# mt2.net
KiCad netlist of a schematic drawn in EAGLE
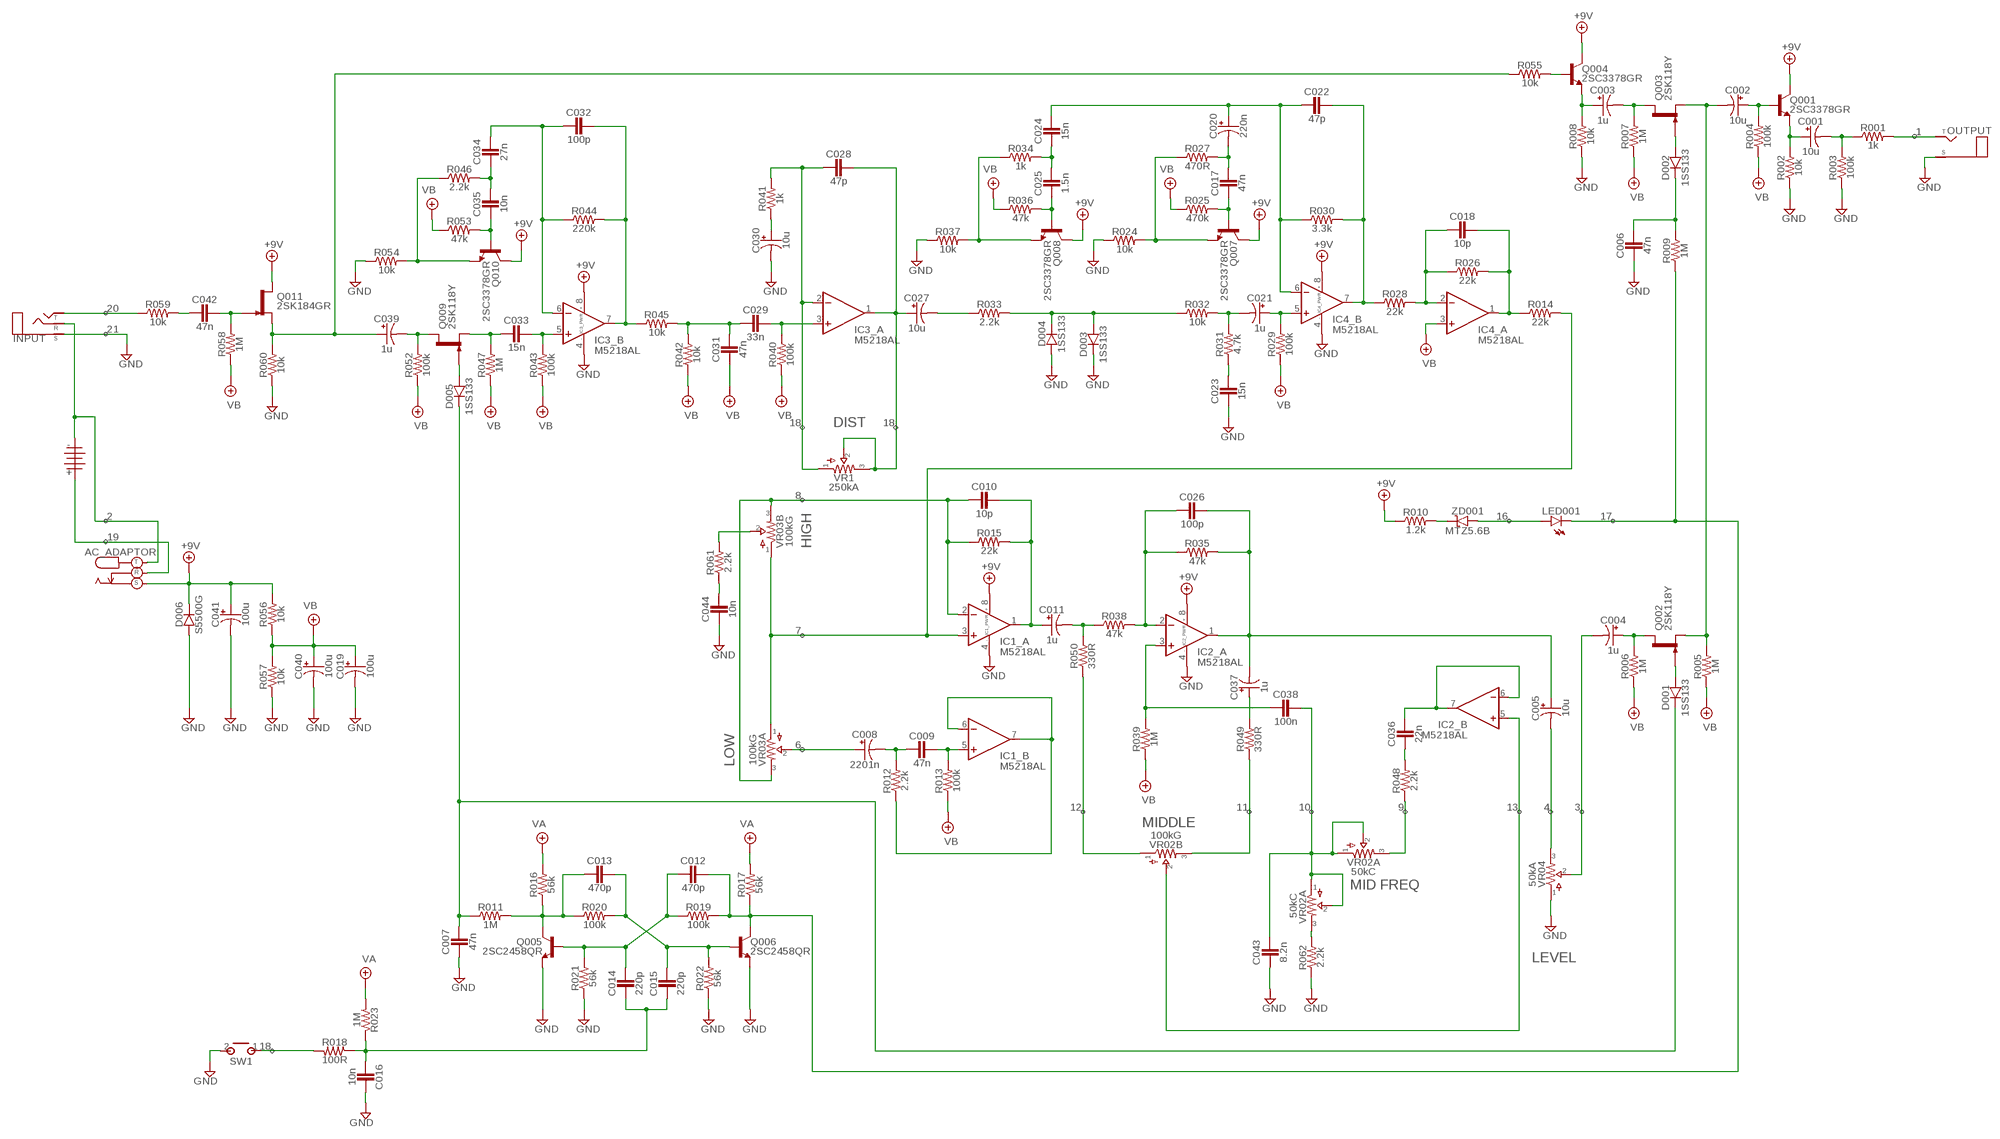
[diagram p0: schematic, sheet 1]

(export (version "E")
  (design (tool "Eeschema 10.0.6"))
  (components
    (comp (ref "1101")
      (value "BATTERY")
      (footprint "eagle-import:TWO_PADS")
      (libsource (lib "eagle-import") (part "BATTERY"))
    )
    (comp (ref "AC_ADAPTOR")
      (value "DC_KOBICONN")
      (footprint "eagle-import:DC_KOBICONN")
      (libsource (lib "eagle-import") (part "DC_KOBICONN"))
    )
    (comp (ref "C001")
      (value "10u")
      (footprint "eagle-import:050_020")
      (libsource (lib "eagle-import") (part "0500"))
    )
    (comp (ref "C002")
      (value "10u")
      (footprint "eagle-import:050_020")
      (libsource (lib "eagle-import") (part "0500"))
    )
    (comp (ref "C003")
      (value "1u")
      (footprint "eagle-import:050_020")
      (libsource (lib "eagle-import") (part "0500"))
    )
    (comp (ref "C004")
      (value "1u")
      (footprint "eagle-import:050_020")
      (libsource (lib "eagle-import") (part "0500"))
    )
    (comp (ref "C005")
      (value "10u")
      (footprint "eagle-import:050_020")
      (libsource (lib "eagle-import") (part "0500"))
    )
    (comp (ref "C006")
      (value "47n")
      (footprint "eagle-import:BOX_SMALL")
      (libsource (lib "eagle-import") (part "CER/FILMBOX.1"))
    )
    (comp (ref "C007")
      (value "47n")
      (footprint "eagle-import:BOX_SMALL")
      (libsource (lib "eagle-import") (part "CER/FILMBOX.1"))
    )
    (comp (ref "C008")
      (value "2201n")
      (footprint "eagle-import:050_020")
      (libsource (lib "eagle-import") (part "0500"))
    )
    (comp (ref "C009")
      (value "47n")
      (footprint "eagle-import:BOX_SMALL")
      (libsource (lib "eagle-import") (part "CER/FILMBOX.1"))
    )
    (comp (ref "C010")
      (value "10p")
      (footprint "eagle-import:BOX_SMALL")
      (libsource (lib "eagle-import") (part "CER/FILMBOX.1"))
    )
    (comp (ref "C011")
      (value "1u")
      (footprint "eagle-import:050_020")
      (libsource (lib "eagle-import") (part "0500"))
    )
    (comp (ref "C012")
      (value "470p")
      (footprint "eagle-import:BOX_SMALL")
      (libsource (lib "eagle-import") (part "CER/FILMBOX.1"))
    )
    (comp (ref "C013")
      (value "470p")
      (footprint "eagle-import:BOX_SMALL")
      (libsource (lib "eagle-import") (part "CER/FILMBOX.1"))
    )
    (comp (ref "C014")
      (value "220p")
      (footprint "eagle-import:BOX_SMALL")
      (libsource (lib "eagle-import") (part "CER/FILMBOX.1"))
    )
    (comp (ref "C015")
      (value "220p")
      (footprint "eagle-import:BOX_SMALL")
      (libsource (lib "eagle-import") (part "CER/FILMBOX.1"))
    )
    (comp (ref "C016")
      (value "10n")
      (footprint "eagle-import:BOX_SMALL")
      (libsource (lib "eagle-import") (part "CER/FILMBOX.1"))
    )
    (comp (ref "C017")
      (value "47n")
      (footprint "eagle-import:BOX_SMALL")
      (libsource (lib "eagle-import") (part "CER/FILMBOX.1"))
    )
    (comp (ref "C018")
      (value "10p")
      (footprint "eagle-import:BOX_SMALL")
      (libsource (lib "eagle-import") (part "CER/FILMBOX.1"))
    )
    (comp (ref "C019")
      (value "100u")
      (footprint "eagle-import:050_020")
      (libsource (lib "eagle-import") (part "0500"))
    )
    (comp (ref "C020")
      (value "220n")
      (footprint "eagle-import:050_020")
      (libsource (lib "eagle-import") (part "0500"))
    )
    (comp (ref "C021")
      (value "1u")
      (footprint "eagle-import:050_020")
      (libsource (lib "eagle-import") (part "0500"))
    )
    (comp (ref "C022")
      (value "47p")
      (footprint "eagle-import:BOX_SMALL")
      (libsource (lib "eagle-import") (part "CER/FILMBOX.1"))
    )
    (comp (ref "C023")
      (value "15n")
      (footprint "eagle-import:BOX_SMALL")
      (libsource (lib "eagle-import") (part "CER/FILMBOX.1"))
    )
    (comp (ref "C024")
      (value "15n")
      (footprint "eagle-import:BOX_SMALL")
      (libsource (lib "eagle-import") (part "CER/FILMBOX.1"))
    )
    (comp (ref "C025")
      (value "1.5n")
      (footprint "eagle-import:BOX_SMALL")
      (libsource (lib "eagle-import") (part "CER/FILMBOX.1"))
    )
    (comp (ref "C026")
      (value "100p")
      (footprint "eagle-import:BOX_SMALL")
      (libsource (lib "eagle-import") (part "CER/FILMBOX.1"))
    )
    (comp (ref "C027")
      (value "10u")
      (footprint "eagle-import:050_020")
      (libsource (lib "eagle-import") (part "0500"))
    )
    (comp (ref "C028")
      (value "47p")
      (footprint "eagle-import:BOX_SMALL")
      (libsource (lib "eagle-import") (part "CER/FILMBOX.1"))
    )
    (comp (ref "C029")
      (value "33n")
      (footprint "eagle-import:BOX_SMALL")
      (libsource (lib "eagle-import") (part "CER/FILMBOX.1"))
    )
    (comp (ref "C030")
      (value "10u")
      (footprint "eagle-import:050_020")
      (libsource (lib "eagle-import") (part "0500"))
    )
    (comp (ref "C031")
      (value "47n")
      (footprint "eagle-import:BOX_SMALL")
      (libsource (lib "eagle-import") (part "CER/FILMBOX.1"))
    )
    (comp (ref "C032")
      (value "100p")
      (footprint "eagle-import:BOX_SMALL")
      (libsource (lib "eagle-import") (part "CER/FILMBOX.1"))
    )
    (comp (ref "C033")
      (value "15n")
      (footprint "eagle-import:BOX_SMALL")
      (libsource (lib "eagle-import") (part "CER/FILMBOX.1"))
    )
    (comp (ref "C034")
      (value "27n")
      (footprint "eagle-import:BOX_SMALL")
      (libsource (lib "eagle-import") (part "CER/FILMBOX.1"))
    )
    (comp (ref "C035")
      (value "10n")
      (footprint "eagle-import:BOX_SMALL")
      (libsource (lib "eagle-import") (part "CER/FILMBOX.1"))
    )
    (comp (ref "C036")
      (value "22n")
      (footprint "eagle-import:BOX_SMALL")
      (libsource (lib "eagle-import") (part "CER/FILMBOX.1"))
    )
    (comp (ref "C037")
      (value "1u")
      (footprint "eagle-import:050_020")
      (libsource (lib "eagle-import") (part "0500"))
    )
    (comp (ref "C038")
      (value "100n")
      (footprint "eagle-import:BOX_SMALL")
      (libsource (lib "eagle-import") (part "CER/FILMBOX.1"))
    )
    (comp (ref "C039")
      (value "1u")
      (footprint "eagle-import:050_020")
      (libsource (lib "eagle-import") (part "0500"))
    )
    (comp (ref "C040")
      (value "100u")
      (footprint "eagle-import:050_020")
      (libsource (lib "eagle-import") (part "0500"))
    )
    (comp (ref "C041")
      (value "100u")
      (footprint "eagle-import:050_020")
      (libsource (lib "eagle-import") (part "0500"))
    )
    (comp (ref "C042")
      (value "47n")
      (footprint "eagle-import:BOX_SMALL")
      (libsource (lib "eagle-import") (part "CER/FILMBOX.1"))
    )
    (comp (ref "C043")
      (value "8.2n")
      (footprint "eagle-import:BOX_SMALL")
      (libsource (lib "eagle-import") (part "CER/FILMBOX.1"))
    )
    (comp (ref "C044")
      (value "10n")
      (footprint "eagle-import:BOX_SMALL")
      (libsource (lib "eagle-import") (part "CER/FILMBOX.1"))
    )
    (comp (ref "D001")
      (value "1SS133")
      (footprint "eagle-import:DO35-2")
      (libsource (lib "eagle-import") (part "DO35.2"))
    )
    (comp (ref "D002")
      (value "1SS133")
      (footprint "eagle-import:DO35-2")
      (libsource (lib "eagle-import") (part "DO35.2"))
    )
    (comp (ref "D003")
      (value "1SS133")
      (footprint "eagle-import:DO35-2")
      (libsource (lib "eagle-import") (part "DO35.2"))
    )
    (comp (ref "D004")
      (value "1SS133")
      (footprint "eagle-import:DO35-2")
      (libsource (lib "eagle-import") (part "DO35.2"))
    )
    (comp (ref "D005")
      (value "1SS133")
      (footprint "eagle-import:DO35-2")
      (libsource (lib "eagle-import") (part "DO35.2"))
    )
    (comp (ref "D006")
      (value "S5500G")
      (footprint "eagle-import:DO35-2")
      (libsource (lib "eagle-import") (part "DO35.2"))
    )
    (comp (ref "IC1")
      (value "M5218AL")
      (footprint "eagle-import:DIL0")
      (libsource (lib "eagle-import") (part "DUALTH"))
    )
    (comp (ref "IC2")
      (value "M5218AL")
      (footprint "eagle-import:DIL0")
      (libsource (lib "eagle-import") (part "DUALTH"))
    )
    (comp (ref "IC3")
      (value "M5218AL")
      (footprint "eagle-import:DIL0")
      (libsource (lib "eagle-import") (part "DUALTH"))
    )
    (comp (ref "IC4")
      (value "M5218AL")
      (footprint "eagle-import:DIL0")
      (libsource (lib "eagle-import") (part "DUALTH"))
    )
    (comp (ref "INPUT")
      (value "STEREO3PADS")
      (footprint "eagle-import:THREEPADS")
      (libsource (lib "eagle-import") (part "STEREO3PADS"))
    )
    (comp (ref "LED001")
      (value "LED")
      (footprint "eagle-import:3MM_D")
      (libsource (lib "eagle-import") (part "LED"))
    )
    (comp (ref "OUTPUT")
      (value "MONO")
      (footprint "eagle-import:TWO_PADS")
      (libsource (lib "eagle-import") (part "MONO"))
    )
    (comp (ref "Q001")
      (value "2SC3378GR")
      (footprint "eagle-import:TO92-")
      (libsource (lib "eagle-import") (part "2N3904"))
    )
    (comp (ref "Q002")
      (value "2SK118Y")
      (footprint "eagle-import:TO92-")
      (libsource (lib "eagle-import") (part "2N5457"))
    )
    (comp (ref "Q003")
      (value "2SK118Y")
      (footprint "eagle-import:TO92-")
      (libsource (lib "eagle-import") (part "2N5457"))
    )
    (comp (ref "Q004")
      (value "2SC3378GR")
      (footprint "eagle-import:TO92-")
      (libsource (lib "eagle-import") (part "2N3904"))
    )
    (comp (ref "Q005")
      (value "2SC2458QR")
      (footprint "eagle-import:TO92-")
      (libsource (lib "eagle-import") (part "2SC828A"))
    )
    (comp (ref "Q006")
      (value "2SC2458QR")
      (footprint "eagle-import:TO92-")
      (libsource (lib "eagle-import") (part "2SC828A"))
    )
    (comp (ref "Q007")
      (value "2SC3378GR")
      (footprint "eagle-import:TO92-")
      (libsource (lib "eagle-import") (part "2N3904"))
    )
    (comp (ref "Q008")
      (value "2SC3378GR")
      (footprint "eagle-import:TO92-")
      (libsource (lib "eagle-import") (part "2N3904"))
    )
    (comp (ref "Q009")
      (value "2SK118Y")
      (footprint "eagle-import:TO92-")
      (libsource (lib "eagle-import") (part "2N5457"))
    )
    (comp (ref "Q010")
      (value "2SC3378GR")
      (footprint "eagle-import:TO92-")
      (libsource (lib "eagle-import") (part "2N3904"))
    )
    (comp (ref "Q011")
      (value "2SK184GR")
      (footprint "eagle-import:TO92-")
      (libsource (lib "eagle-import") (part "2N5457"))
    )
    (comp (ref "R001")
      (value "1k")
      (footprint "eagle-import:R0207_3")
      (libsource (lib "eagle-import") (part "R_.3B"))
    )
    (comp (ref "R002")
      (value "10k")
      (footprint "eagle-import:R0207_3")
      (libsource (lib "eagle-import") (part "R_.3B"))
    )
    (comp (ref "R003")
      (value "100k")
      (footprint "eagle-import:R0207_3")
      (libsource (lib "eagle-import") (part "R_.3B"))
    )
    (comp (ref "R004")
      (value "100k")
      (footprint "eagle-import:R0207_3")
      (libsource (lib "eagle-import") (part "R_.3B"))
    )
    (comp (ref "R005")
      (value "1M")
      (footprint "eagle-import:R0207_3")
      (libsource (lib "eagle-import") (part "R_.3B"))
    )
    (comp (ref "R006")
      (value "1M")
      (footprint "eagle-import:R0207_3")
      (libsource (lib "eagle-import") (part "R_.3B"))
    )
    (comp (ref "R007")
      (value "1M")
      (footprint "eagle-import:R0207_3")
      (libsource (lib "eagle-import") (part "R_.3B"))
    )
    (comp (ref "R008")
      (value "10k")
      (footprint "eagle-import:R0207_3")
      (libsource (lib "eagle-import") (part "R_.3B"))
    )
    (comp (ref "R009")
      (value "1M")
      (footprint "eagle-import:R0207_3")
      (libsource (lib "eagle-import") (part "R_.3B"))
    )
    (comp (ref "R010")
      (value "1.2k")
      (footprint "eagle-import:R0207_3")
      (libsource (lib "eagle-import") (part "R_.3B"))
    )
    (comp (ref "R011")
      (value "1M")
      (footprint "eagle-import:R0207_3")
      (libsource (lib "eagle-import") (part "R_.3B"))
    )
    (comp (ref "R012")
      (value "2.2k")
      (footprint "eagle-import:R0207_3")
      (libsource (lib "eagle-import") (part "R_.3B"))
    )
    (comp (ref "R013")
      (value "100k")
      (footprint "eagle-import:R0207_3")
      (libsource (lib "eagle-import") (part "R_.3B"))
    )
    (comp (ref "R014")
      (value "22k")
      (footprint "eagle-import:R0207_3")
      (libsource (lib "eagle-import") (part "R_.3B"))
    )
    (comp (ref "R015")
      (value "22k")
      (footprint "eagle-import:R0207_3")
      (libsource (lib "eagle-import") (part "R_.3B"))
    )
    (comp (ref "R016")
      (value "56k")
      (footprint "eagle-import:R0207_3")
      (libsource (lib "eagle-import") (part "R_.3B"))
    )
    (comp (ref "R017")
      (value "56k")
      (footprint "eagle-import:R0207_3")
      (libsource (lib "eagle-import") (part "R_.3B"))
    )
    (comp (ref "R018")
      (value "100R")
      (footprint "eagle-import:R0207_3")
      (libsource (lib "eagle-import") (part "R_.3B"))
    )
    (comp (ref "R019")
      (value "100k")
      (footprint "eagle-import:R0207_3")
      (libsource (lib "eagle-import") (part "R_.3B"))
    )
    (comp (ref "R020")
      (value "100k")
      (footprint "eagle-import:R0207_3")
      (libsource (lib "eagle-import") (part "R_.3B"))
    )
    (comp (ref "R021")
      (value "56k")
      (footprint "eagle-import:R0207_3")
      (libsource (lib "eagle-import") (part "R_.3B"))
    )
    (comp (ref "R022")
      (value "56k")
      (footprint "eagle-import:R0207_3")
      (libsource (lib "eagle-import") (part "R_.3B"))
    )
    (comp (ref "R023")
      (value "1M")
      (footprint "eagle-import:R0207_3")
      (libsource (lib "eagle-import") (part "R_.3B"))
    )
    (comp (ref "R024")
      (value "10k")
      (footprint "eagle-import:R0207_3")
      (libsource (lib "eagle-import") (part "R_.3B"))
    )
    (comp (ref "R025")
      (value "470k")
      (footprint "eagle-import:R0207_3")
      (libsource (lib "eagle-import") (part "R_.3B"))
    )
    (comp (ref "R026")
      (value "22k")
      (footprint "eagle-import:R0207_3")
      (libsource (lib "eagle-import") (part "R_.3B"))
    )
    (comp (ref "R027")
      (value "470R")
      (footprint "eagle-import:R0207_3")
      (libsource (lib "eagle-import") (part "R_.3B"))
    )
    (comp (ref "R028")
      (value "22k")
      (footprint "eagle-import:R0207_3")
      (libsource (lib "eagle-import") (part "R_.3B"))
    )
    (comp (ref "R029")
      (value "100k")
      (footprint "eagle-import:R0207_3")
      (libsource (lib "eagle-import") (part "R_.3B"))
    )
    (comp (ref "R030")
      (value "3.3k")
      (footprint "eagle-import:R0207_3")
      (libsource (lib "eagle-import") (part "R_.3B"))
    )
    (comp (ref "R031")
      (value "4.7k")
      (footprint "eagle-import:R0207_3")
      (libsource (lib "eagle-import") (part "R_.3B"))
    )
    (comp (ref "R032")
      (value "10k")
      (footprint "eagle-import:R0207_3")
      (libsource (lib "eagle-import") (part "R_.3B"))
    )
    (comp (ref "R033")
      (value "2.2k")
      (footprint "eagle-import:R0207_3")
      (libsource (lib "eagle-import") (part "R_.3B"))
    )
    (comp (ref "R034")
      (value "1k")
      (footprint "eagle-import:R0207_3")
      (libsource (lib "eagle-import") (part "R_.3B"))
    )
    (comp (ref "R035")
      (value "47k")
      (footprint "eagle-import:R0207_3")
      (libsource (lib "eagle-import") (part "R_.3B"))
    )
    (comp (ref "R036")
      (value "47k")
      (footprint "eagle-import:R0207_3")
      (libsource (lib "eagle-import") (part "R_.3B"))
    )
    (comp (ref "R037")
      (value "10k")
      (footprint "eagle-import:R0207_3")
      (libsource (lib "eagle-import") (part "R_.3B"))
    )
    (comp (ref "R038")
      (value "47k")
      (footprint "eagle-import:R0207_3")
      (libsource (lib "eagle-import") (part "R_.3B"))
    )
    (comp (ref "R039")
      (value "1M")
      (footprint "eagle-import:R0207_3")
      (libsource (lib "eagle-import") (part "R_.3B"))
    )
    (comp (ref "R040")
      (value "100k")
      (footprint "eagle-import:R0207_3")
      (libsource (lib "eagle-import") (part "R_.3B"))
    )
    (comp (ref "R041")
      (value "1k")
      (footprint "eagle-import:R0207_3")
      (libsource (lib "eagle-import") (part "R_.3B"))
    )
    (comp (ref "R042")
      (value "10k")
      (footprint "eagle-import:R0207_3")
      (libsource (lib "eagle-import") (part "R_.3B"))
    )
    (comp (ref "R043")
      (value "100k")
      (footprint "eagle-import:R0207_3")
      (libsource (lib "eagle-import") (part "R_.3B"))
    )
    (comp (ref "R044")
      (value "220k")
      (footprint "eagle-import:R0207_3")
      (libsource (lib "eagle-import") (part "R_.3B"))
    )
    (comp (ref "R045")
      (value "10k")
      (footprint "eagle-import:R0207_3")
      (libsource (lib "eagle-import") (part "R_.3B"))
    )
    (comp (ref "R046")
      (value "2.2k")
      (footprint "eagle-import:R0207_3")
      (libsource (lib "eagle-import") (part "R_.3B"))
    )
    (comp (ref "R047")
      (value "1M")
      (footprint "eagle-import:R0207_3")
      (libsource (lib "eagle-import") (part "R_.3B"))
    )
    (comp (ref "R048")
      (value "2.2k")
      (footprint "eagle-import:R0207_3")
      (libsource (lib "eagle-import") (part "R_.3B"))
    )
    (comp (ref "R049")
      (value "330R")
      (footprint "eagle-import:R0207_3")
      (libsource (lib "eagle-import") (part "R_.3B"))
    )
    (comp (ref "R050")
      (value "330R")
      (footprint "eagle-import:R0207_3")
      (libsource (lib "eagle-import") (part "R_.3B"))
    )
    (comp (ref "R052")
      (value "100k")
      (footprint "eagle-import:R0207_3")
      (libsource (lib "eagle-import") (part "R_.3B"))
    )
    (comp (ref "R053")
      (value "47k")
      (footprint "eagle-import:R0207_3")
      (libsource (lib "eagle-import") (part "R_.3B"))
    )
    (comp (ref "R054")
      (value "10k")
      (footprint "eagle-import:R0207_3")
      (libsource (lib "eagle-import") (part "R_.3B"))
    )
    (comp (ref "R055")
      (value "10k")
      (footprint "eagle-import:R0207_3")
      (libsource (lib "eagle-import") (part "R_.3B"))
    )
    (comp (ref "R056")
      (value "10k")
      (footprint "eagle-import:R0207_3")
      (libsource (lib "eagle-import") (part "R_.3B"))
    )
    (comp (ref "R057")
      (value "10k")
      (footprint "eagle-import:R0207_3")
      (libsource (lib "eagle-import") (part "R_.3B"))
    )
    (comp (ref "R058")
      (value "1M")
      (footprint "eagle-import:R0207_3")
      (libsource (lib "eagle-import") (part "R_.3B"))
    )
    (comp (ref "R059")
      (value "10k")
      (footprint "eagle-import:R0207_3")
      (libsource (lib "eagle-import") (part "R_.3B"))
    )
    (comp (ref "R060")
      (value "10k")
      (footprint "eagle-import:R0207_3")
      (libsource (lib "eagle-import") (part "R_.3B"))
    )
    (comp (ref "R061")
      (value "2.2k")
      (footprint "eagle-import:R0207_3")
      (libsource (lib "eagle-import") (part "R_.3B"))
    )
    (comp (ref "R062")
      (value "2.2k")
      (footprint "eagle-import:R0207_3")
      (libsource (lib "eagle-import") (part "R_.3B"))
    )
    (comp (ref "SW1")
      (value "MOMENTARY")
      (footprint "eagle-import:SPST")
      (libsource (lib "eagle-import") (part "MOMENTARY"))
    )
    (comp (ref "VR1")
      (value "250kA")
      (footprint "eagle-import:16MM")
      (libsource (lib "eagle-import") (part "POTS16MM"))
    )
    (comp (ref "VR02A")
      (value "50kC")
      (footprint "eagle-import:16MM")
      (libsource (lib "eagle-import") (part "POTS16MM"))
    )
    (comp (ref "VR02A ")
      (value "50kC")
      (footprint "eagle-import:16MM")
      (libsource (lib "eagle-import") (part "POTS16MM"))
    )
    (comp (ref "VR02B")
      (value "100kG")
      (footprint "eagle-import:16MM")
      (libsource (lib "eagle-import") (part "POTS16MM"))
    )
    (comp (ref "VR03A")
      (value "100kG")
      (footprint "eagle-import:16MM")
      (libsource (lib "eagle-import") (part "POTS16MM"))
    )
    (comp (ref "VR03B")
      (value "100kG")
      (footprint "eagle-import:16MM")
      (libsource (lib "eagle-import") (part "POTS16MM"))
    )
    (comp (ref "VR04")
      (value "50kA")
      (footprint "eagle-import:16MM")
      (libsource (lib "eagle-import") (part "POTS16MM"))
    )
    (comp (ref "ZD001")
      (value "MTZ5.6B")
      (footprint "eagle-import:DO41-2")
      (libsource (lib "eagle-import") (part "ZENER.2"))
    )
  )
  (nets
    (net (code "1") (name "+9V") (class "Default")
      (node (ref "AC_ADAPTOR") (pin "S") (pinfunction "S_S") (pintype "bidirectional"))
      (node (ref "C041") (pin "+") (pinfunction "+_+") (pintype "passive"))
      (node (ref "D006") (pin "C") (pinfunction "C_C") (pintype "passive"))
      (node (ref "IC1") (pin "8") (pinfunction "V+_8") (pintype "power_in"))
      (node (ref "IC2") (pin "8") (pinfunction "V+_8") (pintype "power_in"))
      (node (ref "IC3") (pin "8") (pinfunction "V+_8") (pintype "power_in"))
      (node (ref "IC4") (pin "8") (pinfunction "V+_8") (pintype "power_in"))
      (node (ref "Q001") (pin "1") (pinfunction "C_1") (pintype "passive"))
      (node (ref "Q004") (pin "1") (pinfunction "C_1") (pintype "passive"))
      (node (ref "Q007") (pin "1") (pinfunction "C_1") (pintype "passive"))
      (node (ref "Q008") (pin "1") (pinfunction "C_1") (pintype "passive"))
      (node (ref "Q010") (pin "1") (pinfunction "C_1") (pintype "passive"))
      (node (ref "Q011") (pin "3") (pinfunction "D_3") (pintype "passive"))
      (node (ref "R010") (pin "1") (pinfunction "1_1") (pintype "passive"))
      (node (ref "R056") (pin "2") (pinfunction "2_2") (pintype "passive"))
    )
    (net (code "2") (name "GND") (class "Default")
      (node (ref "C006") (pin "2") (pinfunction "2_2") (pintype "passive"))
      (node (ref "C007") (pin "2") (pinfunction "2_2") (pintype "passive"))
      (node (ref "C016") (pin "2") (pinfunction "2_2") (pintype "passive"))
      (node (ref "C019") (pin "-") (pinfunction "-_-") (pintype "passive"))
      (node (ref "C023") (pin "2") (pinfunction "2_2") (pintype "passive"))
      (node (ref "C030") (pin "-") (pinfunction "-_-") (pintype "passive"))
      (node (ref "C040") (pin "-") (pinfunction "-_-") (pintype "passive"))
      (node (ref "C041") (pin "-") (pinfunction "-_-") (pintype "passive"))
      (node (ref "C043") (pin "2") (pinfunction "2_2") (pintype "passive"))
      (node (ref "C044") (pin "2") (pinfunction "2_2") (pintype "passive"))
      (node (ref "D003") (pin "C") (pinfunction "C_C") (pintype "passive"))
      (node (ref "D004") (pin "A") (pinfunction "A_A") (pintype "passive"))
      (node (ref "D006") (pin "A") (pinfunction "A_A") (pintype "passive"))
      (node (ref "IC1") (pin "4") (pinfunction "V-_4") (pintype "power_in"))
      (node (ref "IC2") (pin "4") (pinfunction "V-_4") (pintype "power_in"))
      (node (ref "IC3") (pin "4") (pinfunction "V-_4") (pintype "power_in"))
      (node (ref "IC4") (pin "4") (pinfunction "V-_4") (pintype "power_in"))
      (node (ref "INPUT") (pin "SLEEVE") (pinfunction "S_SLEEVE") (pintype "passive"))
      (node (ref "OUTPUT") (pin "S") (pinfunction "SLEEVE_S") (pintype "passive"))
      (node (ref "Q005") (pin "3") (pinfunction "E_3") (pintype "passive"))
      (node (ref "Q006") (pin "3") (pinfunction "E_3") (pintype "passive"))
      (node (ref "R002") (pin "1") (pinfunction "1_1") (pintype "passive"))
      (node (ref "R003") (pin "1") (pinfunction "1_1") (pintype "passive"))
      (node (ref "R008") (pin "1") (pinfunction "1_1") (pintype "passive"))
      (node (ref "R021") (pin "1") (pinfunction "1_1") (pintype "passive"))
      (node (ref "R022") (pin "1") (pinfunction "1_1") (pintype "passive"))
      (node (ref "R024") (pin "1") (pinfunction "1_1") (pintype "passive"))
      (node (ref "R037") (pin "1") (pinfunction "1_1") (pintype "passive"))
      (node (ref "R054") (pin "1") (pinfunction "1_1") (pintype "passive"))
      (node (ref "R057") (pin "1") (pinfunction "1_1") (pintype "passive"))
      (node (ref "R060") (pin "1") (pinfunction "1_1") (pintype "passive"))
      (node (ref "R062") (pin "1") (pinfunction "1_1") (pintype "passive"))
      (node (ref "SW1") (pin "2") (pinfunction "S_2") (pintype "passive"))
      (node (ref "VR04") (pin "1") (pinfunction "1_1") (pintype "passive"))
    )
    (net (code "3") (name "Net-(1101-P$1)") (class "Default")
      (node (ref "1101") (pin "T") (pinfunction "P$1_T") (pintype "bidirectional"))
      (node (ref "AC_ADAPTOR") (pin "R") (pinfunction "R_R") (pintype "bidirectional"))
    )
    (net (code "4") (name "Net-(1101-P$2)") (class "Default")
      (node (ref "1101") (pin "S") (pinfunction "P$2_S") (pintype "bidirectional"))
      (node (ref "AC_ADAPTOR") (pin "T") (pinfunction "T_T") (pintype "bidirectional"))
      (node (ref "INPUT") (pin "RING") (pinfunction "R_RING") (pintype "passive"))
    )
    (net (code "5") (name "Net-(C001-Pad-)") (class "Default")
      (node (ref "C001") (pin "-") (pinfunction "-_-") (pintype "passive"))
      (node (ref "R001") (pin "1") (pinfunction "1_1") (pintype "passive"))
      (node (ref "R003") (pin "2") (pinfunction "2_2") (pintype "passive"))
    )
    (net (code "6") (name "Net-(C004-Pad-)") (class "Default")
      (node (ref "C004") (pin "-") (pinfunction "-_-") (pintype "passive"))
      (node (ref "VR04") (pin "2") (pinfunction "2_2") (pintype "passive"))
    )
    (net (code "7") (name "Net-(C005-Pad-)") (class "Default")
      (node (ref "C005") (pin "-") (pinfunction "-_-") (pintype "passive"))
      (node (ref "VR04") (pin "3") (pinfunction "3_3") (pintype "passive"))
    )
    (net (code "8") (name "Net-(C006-Pad1)") (class "Default")
      (node (ref "C006") (pin "1") (pinfunction "1_1") (pintype "passive"))
      (node (ref "D002") (pin "C") (pinfunction "C_C") (pintype "passive"))
      (node (ref "R009") (pin "2") (pinfunction "2_2") (pintype "passive"))
    )
    (net (code "9") (name "Net-(C007-Pad1)") (class "Default")
      (node (ref "C007") (pin "1") (pinfunction "1_1") (pintype "passive"))
      (node (ref "D001") (pin "C") (pinfunction "C_C") (pintype "passive"))
      (node (ref "D005") (pin "C") (pinfunction "C_C") (pintype "passive"))
      (node (ref "R011") (pin "1") (pinfunction "1_1") (pintype "passive"))
    )
    (net (code "10") (name "Net-(C008-Pad+)") (class "Default")
      (node (ref "C008") (pin "+") (pinfunction "+_+") (pintype "passive"))
      (node (ref "VR03A") (pin "2") (pinfunction "2_2") (pintype "passive"))
    )
    (net (code "11") (name "Net-(C008-Pad-)") (class "Default")
      (node (ref "C008") (pin "-") (pinfunction "-_-") (pintype "passive"))
      (node (ref "C009") (pin "2") (pinfunction "2_2") (pintype "passive"))
      (node (ref "R012") (pin "2") (pinfunction "2_2") (pintype "passive"))
    )
    (net (code "12") (name "Net-(C011-Pad-)") (class "Default")
      (node (ref "C011") (pin "-") (pinfunction "-_-") (pintype "passive"))
      (node (ref "R038") (pin "1") (pinfunction "1_1") (pintype "passive"))
      (node (ref "R050") (pin "2") (pinfunction "2_2") (pintype "passive"))
    )
    (net (code "13") (name "Net-(C014-Pad2)") (class "Default")
      (node (ref "C014") (pin "2") (pinfunction "2_2") (pintype "passive"))
      (node (ref "C015") (pin "2") (pinfunction "2_2") (pintype "passive"))
      (node (ref "C016") (pin "1") (pinfunction "1_1") (pintype "passive"))
      (node (ref "R018") (pin "1") (pinfunction "1_1") (pintype "passive"))
      (node (ref "R023") (pin "1") (pinfunction "1_1") (pintype "passive"))
    )
    (net (code "14") (name "Net-(C017-Pad1)") (class "Default")
      (node (ref "C017") (pin "1") (pinfunction "1_1") (pintype "passive"))
      (node (ref "C020") (pin "-") (pinfunction "-_-") (pintype "passive"))
      (node (ref "R027") (pin "2") (pinfunction "2_2") (pintype "passive"))
    )
    (net (code "15") (name "Net-(C021-Pad-)") (class "Default")
      (node (ref "C021") (pin "-") (pinfunction "-_-") (pintype "passive"))
      (node (ref "R031") (pin "2") (pinfunction "2_2") (pintype "passive"))
      (node (ref "R032") (pin "2") (pinfunction "2_2") (pintype "passive"))
    )
    (net (code "16") (name "Net-(C023-Pad1)") (class "Default")
      (node (ref "C023") (pin "1") (pinfunction "1_1") (pintype "passive"))
      (node (ref "R031") (pin "1") (pinfunction "1_1") (pintype "passive"))
    )
    (net (code "17") (name "Net-(C024-Pad2)") (class "Default")
      (node (ref "C024") (pin "2") (pinfunction "2_2") (pintype "passive"))
      (node (ref "C025") (pin "1") (pinfunction "1_1") (pintype "passive"))
      (node (ref "R034") (pin "2") (pinfunction "2_2") (pintype "passive"))
    )
    (net (code "18") (name "Net-(C027-Pad-)") (class "Default")
      (node (ref "C027") (pin "-") (pinfunction "-_-") (pintype "passive"))
      (node (ref "R033") (pin "1") (pinfunction "1_1") (pintype "passive"))
    )
    (net (code "19") (name "Net-(C029-Pad2)") (class "Default")
      (node (ref "C029") (pin "2") (pinfunction "2_2") (pintype "passive"))
      (node (ref "C031") (pin "1") (pinfunction "1_1") (pintype "passive"))
      (node (ref "R042") (pin "2") (pinfunction "2_2") (pintype "passive"))
      (node (ref "R045") (pin "2") (pinfunction "2_2") (pintype "passive"))
    )
    (net (code "20") (name "Net-(C030-Pad+)") (class "Default")
      (node (ref "C030") (pin "+") (pinfunction "+_+") (pintype "passive"))
      (node (ref "R041") (pin "1") (pinfunction "1_1") (pintype "passive"))
    )
    (net (code "21") (name "Net-(C034-Pad2)") (class "Default")
      (node (ref "C034") (pin "2") (pinfunction "2_2") (pintype "passive"))
      (node (ref "C035") (pin "1") (pinfunction "1_1") (pintype "passive"))
      (node (ref "R046") (pin "2") (pinfunction "2_2") (pintype "passive"))
    )
    (net (code "22") (name "Net-(C036-Pad2)") (class "Default")
      (node (ref "C036") (pin "2") (pinfunction "2_2") (pintype "passive"))
      (node (ref "R048") (pin "2") (pinfunction "2_2") (pintype "passive"))
    )
    (net (code "23") (name "Net-(C037-Pad+)") (class "Default")
      (node (ref "C037") (pin "+") (pinfunction "+_+") (pintype "passive"))
      (node (ref "R049") (pin "2") (pinfunction "2_2") (pintype "passive"))
    )
    (net (code "24") (name "Net-(C038-Pad1)") (class "Default")
      (node (ref "C038") (pin "1") (pinfunction "1_1") (pintype "passive"))
      (node (ref "C043") (pin "1") (pinfunction "1_1") (pintype "passive"))
      (node (ref "VR02A") (pin "1") (pinfunction "1_1") (pintype "passive"))
      (node (ref "VR02A") (pin "2") (pinfunction "2_2") (pintype "passive"))
      (node (ref "VR02A ") (pin "1") (pinfunction "1_1") (pintype "passive"))
      (node (ref "VR02A ") (pin "2") (pinfunction "2_2") (pintype "passive"))
    )
    (net (code "25") (name "Net-(C042-Pad2)") (class "Default")
      (node (ref "C042") (pin "2") (pinfunction "2_2") (pintype "passive"))
      (node (ref "R059") (pin "2") (pinfunction "2_2") (pintype "passive"))
    )
    (net (code "26") (name "Net-(C044-Pad1)") (class "Default")
      (node (ref "C044") (pin "1") (pinfunction "1_1") (pintype "passive"))
      (node (ref "R061") (pin "1") (pinfunction "1_1") (pintype "passive"))
    )
    (net (code "27") (name "Net-(D003-PadA)") (class "Default")
      (node (ref "D003") (pin "A") (pinfunction "A_A") (pintype "passive"))
      (node (ref "D004") (pin "C") (pinfunction "C_C") (pintype "passive"))
      (node (ref "R032") (pin "1") (pinfunction "1_1") (pintype "passive"))
      (node (ref "R033") (pin "2") (pinfunction "2_2") (pintype "passive"))
    )
    (net (code "28") (name "Net-(IC1A-+IN)") (class "Default")
      (node (ref "IC1") (pin "3") (pinfunction "+IN_3") (pintype "input"))
      (node (ref "R014") (pin "2") (pinfunction "2_2") (pintype "passive"))
      (node (ref "VR03A") (pin "1") (pinfunction "1_1") (pintype "passive"))
      (node (ref "VR03B") (pin "1") (pinfunction "1_1") (pintype "passive"))
    )
    (net (code "29") (name "Net-(IC1A--IN)") (class "Default")
      (node (ref "C010") (pin "2") (pinfunction "2_2") (pintype "passive"))
      (node (ref "IC1") (pin "2") (pinfunction "-IN_2") (pintype "input"))
      (node (ref "R015") (pin "1") (pinfunction "1_1") (pintype "passive"))
      (node (ref "VR03A") (pin "3") (pinfunction "3_3") (pintype "passive"))
      (node (ref "VR03B") (pin "3") (pinfunction "3_3") (pintype "passive"))
    )
    (net (code "30") (name "Net-(IC1A-OUT)") (class "Default")
      (node (ref "C010") (pin "1") (pinfunction "1_1") (pintype "passive"))
      (node (ref "C011") (pin "+") (pinfunction "+_+") (pintype "passive"))
      (node (ref "IC1") (pin "1") (pinfunction "OUT_1") (pintype "output"))
      (node (ref "R015") (pin "2") (pinfunction "2_2") (pintype "passive"))
    )
    (net (code "31") (name "Net-(IC1B-+IN)") (class "Default")
      (node (ref "C009") (pin "1") (pinfunction "1_1") (pintype "passive"))
      (node (ref "IC1") (pin "5") (pinfunction "+IN_5") (pintype "input"))
      (node (ref "R013") (pin "2") (pinfunction "2_2") (pintype "passive"))
    )
    (net (code "32") (name "Net-(IC1B--IN)") (class "Default")
      (node (ref "IC1") (pin "6") (pinfunction "-IN_6") (pintype "input"))
      (node (ref "IC1") (pin "7") (pinfunction "OUT_7") (pintype "output"))
      (node (ref "R012") (pin "1") (pinfunction "1_1") (pintype "passive"))
    )
    (net (code "33") (name "Net-(IC2A-+IN)") (class "Default")
      (node (ref "C038") (pin "2") (pinfunction "2_2") (pintype "passive"))
      (node (ref "IC2") (pin "3") (pinfunction "+IN_3") (pintype "input"))
      (node (ref "R039") (pin "2") (pinfunction "2_2") (pintype "passive"))
    )
    (net (code "34") (name "Net-(IC2A--IN)") (class "Default")
      (node (ref "C026") (pin "2") (pinfunction "2_2") (pintype "passive"))
      (node (ref "IC2") (pin "2") (pinfunction "-IN_2") (pintype "input"))
      (node (ref "R035") (pin "1") (pinfunction "1_1") (pintype "passive"))
      (node (ref "R038") (pin "2") (pinfunction "2_2") (pintype "passive"))
    )
    (net (code "35") (name "Net-(IC2A-OUT)") (class "Default")
      (node (ref "C005") (pin "+") (pinfunction "+_+") (pintype "passive"))
      (node (ref "C026") (pin "1") (pinfunction "1_1") (pintype "passive"))
      (node (ref "C037") (pin "-") (pinfunction "-_-") (pintype "passive"))
      (node (ref "IC2") (pin "1") (pinfunction "OUT_1") (pintype "output"))
      (node (ref "R035") (pin "2") (pinfunction "2_2") (pintype "passive"))
    )
    (net (code "36") (name "Net-(IC2B-+IN)") (class "Default")
      (node (ref "IC2") (pin "5") (pinfunction "+IN_5") (pintype "input"))
      (node (ref "VR02B") (pin "2") (pinfunction "2_2") (pintype "passive"))
    )
    (net (code "37") (name "Net-(IC2B--IN)") (class "Default")
      (node (ref "C036") (pin "1") (pinfunction "1_1") (pintype "passive"))
      (node (ref "IC2") (pin "6") (pinfunction "-IN_6") (pintype "input"))
      (node (ref "IC2") (pin "7") (pinfunction "OUT_7") (pintype "output"))
    )
    (net (code "38") (name "Net-(IC3A-+IN)") (class "Default")
      (node (ref "C029") (pin "1") (pinfunction "1_1") (pintype "passive"))
      (node (ref "IC3") (pin "3") (pinfunction "+IN_3") (pintype "input"))
      (node (ref "R040") (pin "2") (pinfunction "2_2") (pintype "passive"))
    )
    (net (code "39") (name "Net-(IC3A--IN)") (class "Default")
      (node (ref "C028") (pin "2") (pinfunction "2_2") (pintype "passive"))
      (node (ref "IC3") (pin "2") (pinfunction "-IN_2") (pintype "input"))
      (node (ref "R041") (pin "2") (pinfunction "2_2") (pintype "passive"))
      (node (ref "VR1") (pin "1") (pinfunction "1_1") (pintype "passive"))
    )
    (net (code "40") (name "Net-(IC3A-OUT)") (class "Default")
      (node (ref "C027") (pin "+") (pinfunction "+_+") (pintype "passive"))
      (node (ref "C028") (pin "1") (pinfunction "1_1") (pintype "passive"))
      (node (ref "IC3") (pin "1") (pinfunction "OUT_1") (pintype "output"))
      (node (ref "VR1") (pin "2") (pinfunction "2_2") (pintype "passive"))
      (node (ref "VR1") (pin "3") (pinfunction "3_3") (pintype "passive"))
    )
    (net (code "41") (name "Net-(IC3B-+IN)") (class "Default")
      (node (ref "C033") (pin "1") (pinfunction "1_1") (pintype "passive"))
      (node (ref "IC3") (pin "5") (pinfunction "+IN_5") (pintype "input"))
      (node (ref "R043") (pin "2") (pinfunction "2_2") (pintype "passive"))
    )
    (net (code "42") (name "Net-(IC3B--IN)") (class "Default")
      (node (ref "C032") (pin "2") (pinfunction "2_2") (pintype "passive"))
      (node (ref "C034") (pin "1") (pinfunction "1_1") (pintype "passive"))
      (node (ref "IC3") (pin "6") (pinfunction "-IN_6") (pintype "input"))
      (node (ref "R044") (pin "1") (pinfunction "1_1") (pintype "passive"))
    )
    (net (code "43") (name "Net-(IC3B-OUT)") (class "Default")
      (node (ref "C032") (pin "1") (pinfunction "1_1") (pintype "passive"))
      (node (ref "IC3") (pin "7") (pinfunction "OUT_7") (pintype "output"))
      (node (ref "R044") (pin "2") (pinfunction "2_2") (pintype "passive"))
      (node (ref "R045") (pin "1") (pinfunction "1_1") (pintype "passive"))
    )
    (net (code "44") (name "Net-(IC4A--IN)") (class "Default")
      (node (ref "C018") (pin "2") (pinfunction "2_2") (pintype "passive"))
      (node (ref "IC4") (pin "2") (pinfunction "-IN_2") (pintype "input"))
      (node (ref "R026") (pin "1") (pinfunction "1_1") (pintype "passive"))
      (node (ref "R028") (pin "2") (pinfunction "2_2") (pintype "passive"))
    )
    (net (code "45") (name "Net-(IC4A-OUT)") (class "Default")
      (node (ref "C018") (pin "1") (pinfunction "1_1") (pintype "passive"))
      (node (ref "IC4") (pin "1") (pinfunction "OUT_1") (pintype "output"))
      (node (ref "R014") (pin "1") (pinfunction "1_1") (pintype "passive"))
      (node (ref "R026") (pin "2") (pinfunction "2_2") (pintype "passive"))
    )
    (net (code "46") (name "Net-(IC4B-+IN)") (class "Default")
      (node (ref "C021") (pin "+") (pinfunction "+_+") (pintype "passive"))
      (node (ref "IC4") (pin "5") (pinfunction "+IN_5") (pintype "input"))
      (node (ref "R029") (pin "2") (pinfunction "2_2") (pintype "passive"))
    )
    (net (code "47") (name "Net-(IC4B--IN)") (class "Default")
      (node (ref "C020") (pin "+") (pinfunction "+_+") (pintype "passive"))
      (node (ref "C022") (pin "2") (pinfunction "2_2") (pintype "passive"))
      (node (ref "C024") (pin "1") (pinfunction "1_1") (pintype "passive"))
      (node (ref "IC4") (pin "6") (pinfunction "-IN_6") (pintype "input"))
      (node (ref "R030") (pin "1") (pinfunction "1_1") (pintype "passive"))
    )
    (net (code "48") (name "Net-(IC4B-OUT)") (class "Default")
      (node (ref "C022") (pin "1") (pinfunction "1_1") (pintype "passive"))
      (node (ref "IC4") (pin "7") (pinfunction "OUT_7") (pintype "output"))
      (node (ref "R028") (pin "1") (pinfunction "1_1") (pintype "passive"))
      (node (ref "R030") (pin "2") (pinfunction "2_2") (pintype "passive"))
    )
    (net (code "49") (name "Net-(INPUT-T)") (class "Default")
      (node (ref "INPUT") (pin "TIP") (pinfunction "T_TIP") (pintype "passive"))
      (node (ref "R059") (pin "1") (pinfunction "1_1") (pintype "passive"))
    )
    (net (code "50") (name "Net-(LED001-A)") (class "Default")
      (node (ref "LED001") (pin "ANODE") (pinfunction "A_ANODE") (pintype "passive"))
      (node (ref "ZD001") (pin "A") (pinfunction "A_A") (pintype "passive"))
    )
    (net (code "51") (name "Net-(LED001-C)") (class "Default")
      (node (ref "C012") (pin "1") (pinfunction "1_1") (pintype "passive"))
      (node (ref "LED001") (pin "P$1") (pinfunction "C_P$1") (pintype "passive"))
      (node (ref "Q006") (pin "2") (pinfunction "C_2") (pintype "passive"))
      (node (ref "R009") (pin "1") (pinfunction "1_1") (pintype "passive"))
      (node (ref "R017") (pin "1") (pinfunction "1_1") (pintype "passive"))
      (node (ref "R019") (pin "2") (pinfunction "2_2") (pintype "passive"))
    )
    (net (code "52") (name "Net-(OUTPUT-TIP)") (class "Default")
      (node (ref "OUTPUT") (pin "T") (pinfunction "TIP_T") (pintype "passive"))
      (node (ref "R001") (pin "2") (pinfunction "2_2") (pintype "passive"))
    )
    (net (code "53") (name "Net-(Q001-B)") (class "Default")
      (node (ref "C002") (pin "+") (pinfunction "+_+") (pintype "passive"))
      (node (ref "Q001") (pin "2") (pinfunction "B_2") (pintype "passive"))
      (node (ref "R004") (pin "2") (pinfunction "2_2") (pintype "passive"))
    )
    (net (code "54") (name "Net-(Q001-E)") (class "Default")
      (node (ref "C001") (pin "+") (pinfunction "+_+") (pintype "passive"))
      (node (ref "Q001") (pin "3") (pinfunction "E_3") (pintype "passive"))
      (node (ref "R002") (pin "2") (pinfunction "2_2") (pintype "passive"))
    )
    (net (code "55") (name "Net-(Q002-D)") (class "Default")
      (node (ref "C004") (pin "+") (pinfunction "+_+") (pintype "passive"))
      (node (ref "Q002") (pin "3") (pinfunction "D_3") (pintype "passive"))
      (node (ref "R006") (pin "2") (pinfunction "2_2") (pintype "passive"))
    )
    (net (code "56") (name "Net-(Q002-G)") (class "Default")
      (node (ref "D001") (pin "A") (pinfunction "A_A") (pintype "passive"))
      (node (ref "Q002") (pin "1") (pinfunction "G_1") (pintype "passive"))
    )
    (net (code "57") (name "Net-(Q002-S)") (class "Default")
      (node (ref "C002") (pin "-") (pinfunction "-_-") (pintype "passive"))
      (node (ref "Q002") (pin "2") (pinfunction "S_2") (pintype "passive"))
      (node (ref "Q003") (pin "2") (pinfunction "S_2") (pintype "passive"))
      (node (ref "R005") (pin "2") (pinfunction "2_2") (pintype "passive"))
    )
    (net (code "58") (name "Net-(Q003-D)") (class "Default")
      (node (ref "C003") (pin "-") (pinfunction "-_-") (pintype "passive"))
      (node (ref "Q003") (pin "3") (pinfunction "D_3") (pintype "passive"))
      (node (ref "R007") (pin "2") (pinfunction "2_2") (pintype "passive"))
    )
    (net (code "59") (name "Net-(Q003-G)") (class "Default")
      (node (ref "D002") (pin "A") (pinfunction "A_A") (pintype "passive"))
      (node (ref "Q003") (pin "1") (pinfunction "G_1") (pintype "passive"))
    )
    (net (code "60") (name "Net-(Q004-B)") (class "Default")
      (node (ref "Q004") (pin "2") (pinfunction "B_2") (pintype "passive"))
      (node (ref "R055") (pin "2") (pinfunction "2_2") (pintype "passive"))
    )
    (net (code "61") (name "Net-(Q004-E)") (class "Default")
      (node (ref "C003") (pin "+") (pinfunction "+_+") (pintype "passive"))
      (node (ref "Q004") (pin "3") (pinfunction "E_3") (pintype "passive"))
      (node (ref "R008") (pin "2") (pinfunction "2_2") (pintype "passive"))
    )
    (net (code "62") (name "Net-(Q005-B)") (class "Default")
      (node (ref "C012") (pin "2") (pinfunction "2_2") (pintype "passive"))
      (node (ref "C014") (pin "1") (pinfunction "1_1") (pintype "passive"))
      (node (ref "Q005") (pin "1") (pinfunction "B_1") (pintype "passive"))
      (node (ref "R019") (pin "1") (pinfunction "1_1") (pintype "passive"))
      (node (ref "R021") (pin "2") (pinfunction "2_2") (pintype "passive"))
    )
    (net (code "63") (name "Net-(Q005-C)") (class "Default")
      (node (ref "C013") (pin "2") (pinfunction "2_2") (pintype "passive"))
      (node (ref "Q005") (pin "2") (pinfunction "C_2") (pintype "passive"))
      (node (ref "R011") (pin "2") (pinfunction "2_2") (pintype "passive"))
      (node (ref "R016") (pin "1") (pinfunction "1_1") (pintype "passive"))
      (node (ref "R020") (pin "1") (pinfunction "1_1") (pintype "passive"))
    )
    (net (code "64") (name "Net-(Q006-B)") (class "Default")
      (node (ref "C013") (pin "1") (pinfunction "1_1") (pintype "passive"))
      (node (ref "C015") (pin "1") (pinfunction "1_1") (pintype "passive"))
      (node (ref "Q006") (pin "1") (pinfunction "B_1") (pintype "passive"))
      (node (ref "R020") (pin "2") (pinfunction "2_2") (pintype "passive"))
      (node (ref "R022") (pin "2") (pinfunction "2_2") (pintype "passive"))
    )
    (net (code "65") (name "Net-(Q007-B)") (class "Default")
      (node (ref "C017") (pin "2") (pinfunction "2_2") (pintype "passive"))
      (node (ref "Q007") (pin "2") (pinfunction "B_2") (pintype "passive"))
      (node (ref "R025") (pin "2") (pinfunction "2_2") (pintype "passive"))
    )
    (net (code "66") (name "Net-(Q007-E)") (class "Default")
      (node (ref "Q007") (pin "3") (pinfunction "E_3") (pintype "passive"))
      (node (ref "R024") (pin "2") (pinfunction "2_2") (pintype "passive"))
      (node (ref "R027") (pin "1") (pinfunction "1_1") (pintype "passive"))
    )
    (net (code "67") (name "Net-(Q008-B)") (class "Default")
      (node (ref "C025") (pin "2") (pinfunction "2_2") (pintype "passive"))
      (node (ref "Q008") (pin "2") (pinfunction "B_2") (pintype "passive"))
      (node (ref "R036") (pin "2") (pinfunction "2_2") (pintype "passive"))
    )
    (net (code "68") (name "Net-(Q008-E)") (class "Default")
      (node (ref "Q008") (pin "3") (pinfunction "E_3") (pintype "passive"))
      (node (ref "R034") (pin "1") (pinfunction "1_1") (pintype "passive"))
      (node (ref "R037") (pin "2") (pinfunction "2_2") (pintype "passive"))
    )
    (net (code "69") (name "Net-(Q009-D)") (class "Default")
      (node (ref "C039") (pin "-") (pinfunction "-_-") (pintype "passive"))
      (node (ref "Q009") (pin "3") (pinfunction "D_3") (pintype "passive"))
      (node (ref "R052") (pin "2") (pinfunction "2_2") (pintype "passive"))
    )
    (net (code "70") (name "Net-(Q009-G)") (class "Default")
      (node (ref "D005") (pin "A") (pinfunction "A_A") (pintype "passive"))
      (node (ref "Q009") (pin "1") (pinfunction "G_1") (pintype "passive"))
    )
    (net (code "71") (name "Net-(Q009-S)") (class "Default")
      (node (ref "C033") (pin "2") (pinfunction "2_2") (pintype "passive"))
      (node (ref "Q009") (pin "2") (pinfunction "S_2") (pintype "passive"))
      (node (ref "R047") (pin "2") (pinfunction "2_2") (pintype "passive"))
    )
    (net (code "72") (name "Net-(Q010-B)") (class "Default")
      (node (ref "C035") (pin "2") (pinfunction "2_2") (pintype "passive"))
      (node (ref "Q010") (pin "2") (pinfunction "B_2") (pintype "passive"))
      (node (ref "R053") (pin "2") (pinfunction "2_2") (pintype "passive"))
    )
    (net (code "73") (name "Net-(Q010-E)") (class "Default")
      (node (ref "Q010") (pin "3") (pinfunction "E_3") (pintype "passive"))
      (node (ref "R046") (pin "1") (pinfunction "1_1") (pintype "passive"))
      (node (ref "R054") (pin "2") (pinfunction "2_2") (pintype "passive"))
    )
    (net (code "74") (name "Net-(Q011-G)") (class "Default")
      (node (ref "C042") (pin "1") (pinfunction "1_1") (pintype "passive"))
      (node (ref "Q011") (pin "1") (pinfunction "G_1") (pintype "passive"))
      (node (ref "R058") (pin "2") (pinfunction "2_2") (pintype "passive"))
    )
    (net (code "75") (name "Net-(Q011-S)") (class "Default")
      (node (ref "C039") (pin "+") (pinfunction "+_+") (pintype "passive"))
      (node (ref "Q011") (pin "2") (pinfunction "S_2") (pintype "passive"))
      (node (ref "R055") (pin "1") (pinfunction "1_1") (pintype "passive"))
      (node (ref "R060") (pin "2") (pinfunction "2_2") (pintype "passive"))
    )
    (net (code "76") (name "Net-(R010-Pad2)") (class "Default")
      (node (ref "R010") (pin "2") (pinfunction "2_2") (pintype "passive"))
      (node (ref "ZD001") (pin "C") (pinfunction "C_C") (pintype "passive"))
    )
    (net (code "77") (name "Net-(R048-Pad1)") (class "Default")
      (node (ref "R048") (pin "1") (pinfunction "1_1") (pintype "passive"))
      (node (ref "VR02A") (pin "3") (pinfunction "3_3") (pintype "passive"))
    )
    (net (code "78") (name "Net-(R049-Pad1)") (class "Default")
      (node (ref "R049") (pin "1") (pinfunction "1_1") (pintype "passive"))
      (node (ref "VR02B") (pin "3") (pinfunction "3_3") (pintype "passive"))
    )
    (net (code "79") (name "Net-(R050-Pad1)") (class "Default")
      (node (ref "R050") (pin "1") (pinfunction "1_1") (pintype "passive"))
      (node (ref "VR02B") (pin "1") (pinfunction "1_1") (pintype "passive"))
    )
    (net (code "80") (name "Net-(R061-Pad2)") (class "Default")
      (node (ref "R061") (pin "2") (pinfunction "2_2") (pintype "passive"))
      (node (ref "VR03B") (pin "2") (pinfunction "2_2") (pintype "passive"))
    )
    (net (code "81") (name "Net-(R062-Pad2)") (class "Default")
      (node (ref "R062") (pin "2") (pinfunction "2_2") (pintype "passive"))
      (node (ref "VR02A ") (pin "3") (pinfunction "3_3") (pintype "passive"))
    )
    (net (code "82") (name "Net-(SW1-P)") (class "Default")
      (node (ref "R018") (pin "2") (pinfunction "2_2") (pintype "passive"))
      (node (ref "SW1") (pin "1") (pinfunction "P_1") (pintype "passive"))
    )
    (net (code "83") (name "VA") (class "Default")
      (node (ref "R016") (pin "2") (pinfunction "2_2") (pintype "passive"))
      (node (ref "R017") (pin "2") (pinfunction "2_2") (pintype "passive"))
      (node (ref "R023") (pin "2") (pinfunction "2_2") (pintype "passive"))
    )
    (net (code "84") (name "VB") (class "Default")
      (node (ref "C019") (pin "+") (pinfunction "+_+") (pintype "passive"))
      (node (ref "C031") (pin "2") (pinfunction "2_2") (pintype "passive"))
      (node (ref "C040") (pin "+") (pinfunction "+_+") (pintype "passive"))
      (node (ref "IC4") (pin "3") (pinfunction "+IN_3") (pintype "input"))
      (node (ref "R004") (pin "1") (pinfunction "1_1") (pintype "passive"))
      (node (ref "R005") (pin "1") (pinfunction "1_1") (pintype "passive"))
      (node (ref "R006") (pin "1") (pinfunction "1_1") (pintype "passive"))
      (node (ref "R007") (pin "1") (pinfunction "1_1") (pintype "passive"))
      (node (ref "R013") (pin "1") (pinfunction "1_1") (pintype "passive"))
      (node (ref "R025") (pin "1") (pinfunction "1_1") (pintype "passive"))
      (node (ref "R029") (pin "1") (pinfunction "1_1") (pintype "passive"))
      (node (ref "R036") (pin "1") (pinfunction "1_1") (pintype "passive"))
      (node (ref "R039") (pin "1") (pinfunction "1_1") (pintype "passive"))
      (node (ref "R040") (pin "1") (pinfunction "1_1") (pintype "passive"))
      (node (ref "R042") (pin "1") (pinfunction "1_1") (pintype "passive"))
      (node (ref "R043") (pin "1") (pinfunction "1_1") (pintype "passive"))
      (node (ref "R047") (pin "1") (pinfunction "1_1") (pintype "passive"))
      (node (ref "R052") (pin "1") (pinfunction "1_1") (pintype "passive"))
      (node (ref "R053") (pin "1") (pinfunction "1_1") (pintype "passive"))
      (node (ref "R056") (pin "1") (pinfunction "1_1") (pintype "passive"))
      (node (ref "R057") (pin "2") (pinfunction "2_2") (pintype "passive"))
      (node (ref "R058") (pin "1") (pinfunction "1_1") (pintype "passive"))
    )
  )
)
